# SCH_Calculator_YSWS_2026-07-11.net
KiCad netlist of a schematic drawn in EasyEDA
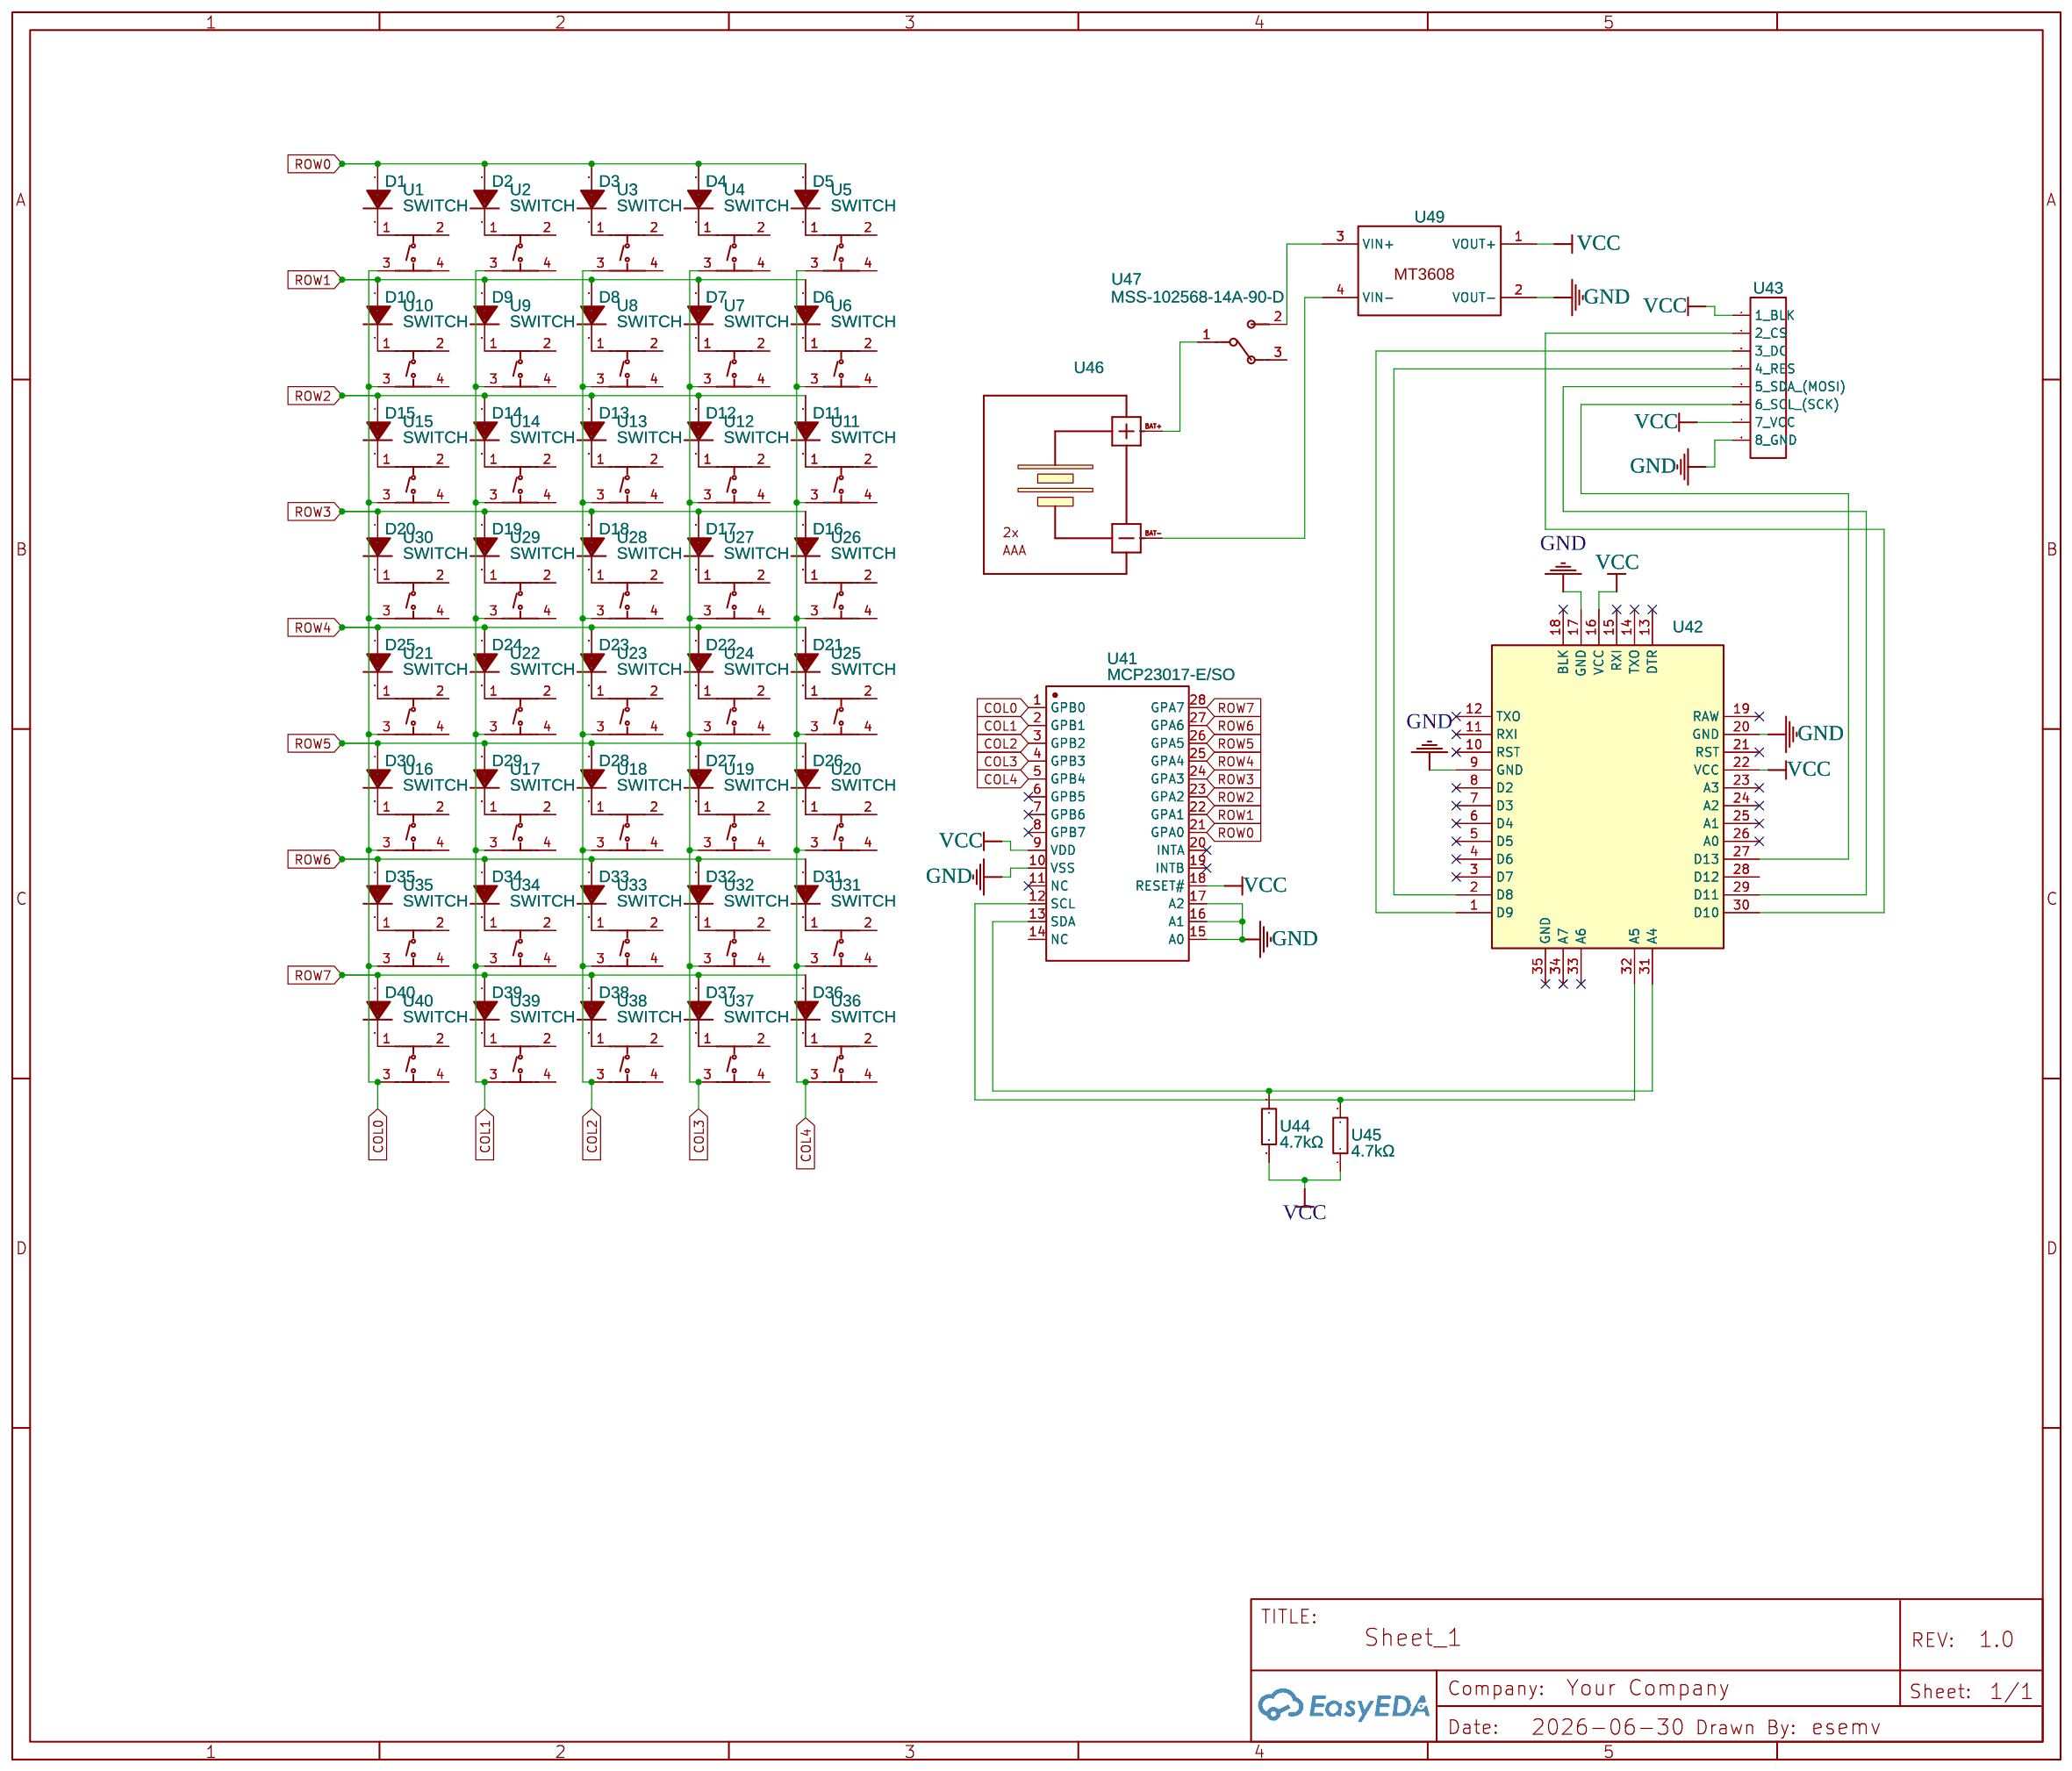
[diagram p0: schematic sheet]

(export (version "E")
  (design (tool "Eeschema 10.0.6"))
  (components
    (comp (ref "D1")
      (value "1N4148")
      (fields (field (name "Manufacturer") "ST(先科)"))
      (libsource (lib "") (part "1N4148"))
    )
    (comp (ref "D2")
      (value "1N4148")
      (fields (field (name "Manufacturer") "ST(先科)"))
      (libsource (lib "") (part "1N4148"))
    )
    (comp (ref "D3")
      (value "1N4148")
      (fields (field (name "Manufacturer") "ST(先科)"))
      (libsource (lib "") (part "1N4148"))
    )
    (comp (ref "D4")
      (value "1N4148")
      (fields (field (name "Manufacturer") "ST(先科)"))
      (libsource (lib "") (part "1N4148"))
    )
    (comp (ref "D5")
      (value "1N4148")
      (fields (field (name "Manufacturer") "ST(先科)"))
      (libsource (lib "") (part "1N4148"))
    )
    (comp (ref "D6")
      (value "1N4148")
      (fields (field (name "Manufacturer") "ST(先科)"))
      (libsource (lib "") (part "1N4148"))
    )
    (comp (ref "D7")
      (value "1N4148")
      (fields (field (name "Manufacturer") "ST(先科)"))
      (libsource (lib "") (part "1N4148"))
    )
    (comp (ref "D8")
      (value "1N4148")
      (fields (field (name "Manufacturer") "ST(先科)"))
      (libsource (lib "") (part "1N4148"))
    )
    (comp (ref "D9")
      (value "1N4148")
      (fields (field (name "Manufacturer") "ST(先科)"))
      (libsource (lib "") (part "1N4148"))
    )
    (comp (ref "D10")
      (value "1N4148")
      (fields (field (name "Manufacturer") "ST(先科)"))
      (libsource (lib "") (part "1N4148"))
    )
    (comp (ref "D11")
      (value "1N4148")
      (fields (field (name "Manufacturer") "ST(先科)"))
      (libsource (lib "") (part "1N4148"))
    )
    (comp (ref "D12")
      (value "1N4148")
      (fields (field (name "Manufacturer") "ST(先科)"))
      (libsource (lib "") (part "1N4148"))
    )
    (comp (ref "D13")
      (value "1N4148")
      (fields (field (name "Manufacturer") "ST(先科)"))
      (libsource (lib "") (part "1N4148"))
    )
    (comp (ref "D14")
      (value "1N4148")
      (fields (field (name "Manufacturer") "ST(先科)"))
      (libsource (lib "") (part "1N4148"))
    )
    (comp (ref "D15")
      (value "1N4148")
      (fields (field (name "Manufacturer") "ST(先科)"))
      (libsource (lib "") (part "1N4148"))
    )
    (comp (ref "D16")
      (value "1N4148")
      (fields (field (name "Manufacturer") "ST(先科)"))
      (libsource (lib "") (part "1N4148"))
    )
    (comp (ref "D17")
      (value "1N4148")
      (fields (field (name "Manufacturer") "ST(先科)"))
      (libsource (lib "") (part "1N4148"))
    )
    (comp (ref "D18")
      (value "1N4148")
      (fields (field (name "Manufacturer") "ST(先科)"))
      (libsource (lib "") (part "1N4148"))
    )
    (comp (ref "D19")
      (value "1N4148")
      (fields (field (name "Manufacturer") "ST(先科)"))
      (libsource (lib "") (part "1N4148"))
    )
    (comp (ref "D20")
      (value "1N4148")
      (fields (field (name "Manufacturer") "ST(先科)"))
      (libsource (lib "") (part "1N4148"))
    )
    (comp (ref "D21")
      (value "1N4148")
      (fields (field (name "Manufacturer") "ST(先科)"))
      (libsource (lib "") (part "1N4148"))
    )
    (comp (ref "D22")
      (value "1N4148")
      (fields (field (name "Manufacturer") "ST(先科)"))
      (libsource (lib "") (part "1N4148"))
    )
    (comp (ref "D23")
      (value "1N4148")
      (fields (field (name "Manufacturer") "ST(先科)"))
      (libsource (lib "") (part "1N4148"))
    )
    (comp (ref "D24")
      (value "1N4148")
      (fields (field (name "Manufacturer") "ST(先科)"))
      (libsource (lib "") (part "1N4148"))
    )
    (comp (ref "D25")
      (value "1N4148")
      (fields (field (name "Manufacturer") "ST(先科)"))
      (libsource (lib "") (part "1N4148"))
    )
    (comp (ref "D26")
      (value "1N4148")
      (fields (field (name "Manufacturer") "ST(先科)"))
      (libsource (lib "") (part "1N4148"))
    )
    (comp (ref "D27")
      (value "1N4148")
      (fields (field (name "Manufacturer") "ST(先科)"))
      (libsource (lib "") (part "1N4148"))
    )
    (comp (ref "D28")
      (value "1N4148")
      (fields (field (name "Manufacturer") "ST(先科)"))
      (libsource (lib "") (part "1N4148"))
    )
    (comp (ref "D29")
      (value "1N4148")
      (fields (field (name "Manufacturer") "ST(先科)"))
      (libsource (lib "") (part "1N4148"))
    )
    (comp (ref "D30")
      (value "1N4148")
      (fields (field (name "Manufacturer") "ST(先科)"))
      (libsource (lib "") (part "1N4148"))
    )
    (comp (ref "D31")
      (value "1N4148")
      (fields (field (name "Manufacturer") "ST(先科)"))
      (libsource (lib "") (part "1N4148"))
    )
    (comp (ref "D32")
      (value "1N4148")
      (fields (field (name "Manufacturer") "ST(先科)"))
      (libsource (lib "") (part "1N4148"))
    )
    (comp (ref "D33")
      (value "1N4148")
      (fields (field (name "Manufacturer") "ST(先科)"))
      (libsource (lib "") (part "1N4148"))
    )
    (comp (ref "D34")
      (value "1N4148")
      (fields (field (name "Manufacturer") "ST(先科)"))
      (libsource (lib "") (part "1N4148"))
    )
    (comp (ref "D35")
      (value "1N4148")
      (fields (field (name "Manufacturer") "ST(先科)"))
      (libsource (lib "") (part "1N4148"))
    )
    (comp (ref "D36")
      (value "1N4148")
      (fields (field (name "Manufacturer") "ST(先科)"))
      (libsource (lib "") (part "1N4148"))
    )
    (comp (ref "D37")
      (value "1N4148")
      (fields (field (name "Manufacturer") "ST(先科)"))
      (libsource (lib "") (part "1N4148"))
    )
    (comp (ref "D38")
      (value "1N4148")
      (fields (field (name "Manufacturer") "ST(先科)"))
      (libsource (lib "") (part "1N4148"))
    )
    (comp (ref "D39")
      (value "1N4148")
      (fields (field (name "Manufacturer") "ST(先科)"))
      (libsource (lib "") (part "1N4148"))
    )
    (comp (ref "D40")
      (value "1N4148")
      (fields (field (name "Manufacturer") "ST(先科)"))
      (libsource (lib "") (part "1N4148"))
    )
    (comp (ref "U1")
      (value "SWITCH")
      (fields
        (field (name "Manufacturer Part") "ZX-QC1212-7.0CJ")
        (field (name "Manufacturer") "Megastar(兆星)")
      )
      (libsource (lib "") (part "ZX-QC1212-7.0CJ"))
    )
    (comp (ref "U2")
      (value "SWITCH")
      (fields
        (field (name "Manufacturer Part") "ZX-QC1212-7.0CJ")
        (field (name "Manufacturer") "Megastar(兆星)")
      )
      (libsource (lib "") (part "ZX-QC1212-7.0CJ"))
    )
    (comp (ref "U3")
      (value "SWITCH")
      (fields
        (field (name "Manufacturer Part") "ZX-QC1212-7.0CJ")
        (field (name "Manufacturer") "Megastar(兆星)")
      )
      (libsource (lib "") (part "ZX-QC1212-7.0CJ"))
    )
    (comp (ref "U4")
      (value "SWITCH")
      (fields
        (field (name "Manufacturer Part") "ZX-QC1212-7.0CJ")
        (field (name "Manufacturer") "Megastar(兆星)")
      )
      (libsource (lib "") (part "ZX-QC1212-7.0CJ"))
    )
    (comp (ref "U5")
      (value "SWITCH")
      (fields
        (field (name "Manufacturer Part") "ZX-QC1212-7.0CJ")
        (field (name "Manufacturer") "Megastar(兆星)")
      )
      (libsource (lib "") (part "ZX-QC1212-7.0CJ"))
    )
    (comp (ref "U6")
      (value "SWITCH")
      (fields
        (field (name "Manufacturer Part") "ZX-QC1212-7.0CJ")
        (field (name "Manufacturer") "Megastar(兆星)")
      )
      (libsource (lib "") (part "ZX-QC1212-7.0CJ"))
    )
    (comp (ref "U7")
      (value "SWITCH")
      (fields
        (field (name "Manufacturer Part") "ZX-QC1212-7.0CJ")
        (field (name "Manufacturer") "Megastar(兆星)")
      )
      (libsource (lib "") (part "ZX-QC1212-7.0CJ"))
    )
    (comp (ref "U8")
      (value "SWITCH")
      (fields
        (field (name "Manufacturer Part") "ZX-QC1212-7.0CJ")
        (field (name "Manufacturer") "Megastar(兆星)")
      )
      (libsource (lib "") (part "ZX-QC1212-7.0CJ"))
    )
    (comp (ref "U9")
      (value "SWITCH")
      (fields
        (field (name "Manufacturer Part") "ZX-QC1212-7.0CJ")
        (field (name "Manufacturer") "Megastar(兆星)")
      )
      (libsource (lib "") (part "ZX-QC1212-7.0CJ"))
    )
    (comp (ref "U10")
      (value "SWITCH")
      (fields
        (field (name "Manufacturer Part") "ZX-QC1212-7.0CJ")
        (field (name "Manufacturer") "Megastar(兆星)")
      )
      (libsource (lib "") (part "ZX-QC1212-7.0CJ"))
    )
    (comp (ref "U11")
      (value "SWITCH")
      (fields
        (field (name "Manufacturer Part") "ZX-QC1212-7.0CJ")
        (field (name "Manufacturer") "Megastar(兆星)")
      )
      (libsource (lib "") (part "ZX-QC1212-7.0CJ"))
    )
    (comp (ref "U12")
      (value "SWITCH")
      (fields
        (field (name "Manufacturer Part") "ZX-QC1212-7.0CJ")
        (field (name "Manufacturer") "Megastar(兆星)")
      )
      (libsource (lib "") (part "ZX-QC1212-7.0CJ"))
    )
    (comp (ref "U13")
      (value "SWITCH")
      (fields
        (field (name "Manufacturer Part") "ZX-QC1212-7.0CJ")
        (field (name "Manufacturer") "Megastar(兆星)")
      )
      (libsource (lib "") (part "ZX-QC1212-7.0CJ"))
    )
    (comp (ref "U14")
      (value "SWITCH")
      (fields
        (field (name "Manufacturer Part") "ZX-QC1212-7.0CJ")
        (field (name "Manufacturer") "Megastar(兆星)")
      )
      (libsource (lib "") (part "ZX-QC1212-7.0CJ"))
    )
    (comp (ref "U15")
      (value "SWITCH")
      (fields
        (field (name "Manufacturer Part") "ZX-QC1212-7.0CJ")
        (field (name "Manufacturer") "Megastar(兆星)")
      )
      (libsource (lib "") (part "ZX-QC1212-7.0CJ"))
    )
    (comp (ref "U16")
      (value "SWITCH")
      (fields
        (field (name "Manufacturer Part") "ZX-QC1212-7.0CJ")
        (field (name "Manufacturer") "Megastar(兆星)")
      )
      (libsource (lib "") (part "ZX-QC1212-7.0CJ"))
    )
    (comp (ref "U17")
      (value "SWITCH")
      (fields
        (field (name "Manufacturer Part") "ZX-QC1212-7.0CJ")
        (field (name "Manufacturer") "Megastar(兆星)")
      )
      (libsource (lib "") (part "ZX-QC1212-7.0CJ"))
    )
    (comp (ref "U18")
      (value "SWITCH")
      (fields
        (field (name "Manufacturer Part") "ZX-QC1212-7.0CJ")
        (field (name "Manufacturer") "Megastar(兆星)")
      )
      (libsource (lib "") (part "ZX-QC1212-7.0CJ"))
    )
    (comp (ref "U19")
      (value "SWITCH")
      (fields
        (field (name "Manufacturer Part") "ZX-QC1212-7.0CJ")
        (field (name "Manufacturer") "Megastar(兆星)")
      )
      (libsource (lib "") (part "ZX-QC1212-7.0CJ"))
    )
    (comp (ref "U20")
      (value "SWITCH")
      (fields
        (field (name "Manufacturer Part") "ZX-QC1212-7.0CJ")
        (field (name "Manufacturer") "Megastar(兆星)")
      )
      (libsource (lib "") (part "ZX-QC1212-7.0CJ"))
    )
    (comp (ref "U21")
      (value "SWITCH")
      (fields
        (field (name "Manufacturer Part") "ZX-QC1212-7.0CJ")
        (field (name "Manufacturer") "Megastar(兆星)")
      )
      (libsource (lib "") (part "ZX-QC1212-7.0CJ"))
    )
    (comp (ref "U22")
      (value "SWITCH")
      (fields
        (field (name "Manufacturer Part") "ZX-QC1212-7.0CJ")
        (field (name "Manufacturer") "Megastar(兆星)")
      )
      (libsource (lib "") (part "ZX-QC1212-7.0CJ"))
    )
    (comp (ref "U23")
      (value "SWITCH")
      (fields
        (field (name "Manufacturer Part") "ZX-QC1212-7.0CJ")
        (field (name "Manufacturer") "Megastar(兆星)")
      )
      (libsource (lib "") (part "ZX-QC1212-7.0CJ"))
    )
    (comp (ref "U24")
      (value "SWITCH")
      (fields
        (field (name "Manufacturer Part") "ZX-QC1212-7.0CJ")
        (field (name "Manufacturer") "Megastar(兆星)")
      )
      (libsource (lib "") (part "ZX-QC1212-7.0CJ"))
    )
    (comp (ref "U25")
      (value "SWITCH")
      (fields
        (field (name "Manufacturer Part") "ZX-QC1212-7.0CJ")
        (field (name "Manufacturer") "Megastar(兆星)")
      )
      (libsource (lib "") (part "ZX-QC1212-7.0CJ"))
    )
    (comp (ref "U26")
      (value "SWITCH")
      (fields
        (field (name "Manufacturer Part") "ZX-QC1212-7.0CJ")
        (field (name "Manufacturer") "Megastar(兆星)")
      )
      (libsource (lib "") (part "ZX-QC1212-7.0CJ"))
    )
    (comp (ref "U27")
      (value "SWITCH")
      (fields
        (field (name "Manufacturer Part") "ZX-QC1212-7.0CJ")
        (field (name "Manufacturer") "Megastar(兆星)")
      )
      (libsource (lib "") (part "ZX-QC1212-7.0CJ"))
    )
    (comp (ref "U28")
      (value "SWITCH")
      (fields
        (field (name "Manufacturer Part") "ZX-QC1212-7.0CJ")
        (field (name "Manufacturer") "Megastar(兆星)")
      )
      (libsource (lib "") (part "ZX-QC1212-7.0CJ"))
    )
    (comp (ref "U29")
      (value "SWITCH")
      (fields
        (field (name "Manufacturer Part") "ZX-QC1212-7.0CJ")
        (field (name "Manufacturer") "Megastar(兆星)")
      )
      (libsource (lib "") (part "ZX-QC1212-7.0CJ"))
    )
    (comp (ref "U30")
      (value "SWITCH")
      (fields
        (field (name "Manufacturer Part") "ZX-QC1212-7.0CJ")
        (field (name "Manufacturer") "Megastar(兆星)")
      )
      (libsource (lib "") (part "ZX-QC1212-7.0CJ"))
    )
    (comp (ref "U31")
      (value "SWITCH")
      (fields
        (field (name "Manufacturer Part") "ZX-QC1212-7.0CJ")
        (field (name "Manufacturer") "Megastar(兆星)")
      )
      (libsource (lib "") (part "ZX-QC1212-7.0CJ"))
    )
    (comp (ref "U32")
      (value "SWITCH")
      (fields
        (field (name "Manufacturer Part") "ZX-QC1212-7.0CJ")
        (field (name "Manufacturer") "Megastar(兆星)")
      )
      (libsource (lib "") (part "ZX-QC1212-7.0CJ"))
    )
    (comp (ref "U33")
      (value "SWITCH")
      (fields
        (field (name "Manufacturer Part") "ZX-QC1212-7.0CJ")
        (field (name "Manufacturer") "Megastar(兆星)")
      )
      (libsource (lib "") (part "ZX-QC1212-7.0CJ"))
    )
    (comp (ref "U34")
      (value "SWITCH")
      (fields
        (field (name "Manufacturer Part") "ZX-QC1212-7.0CJ")
        (field (name "Manufacturer") "Megastar(兆星)")
      )
      (libsource (lib "") (part "ZX-QC1212-7.0CJ"))
    )
    (comp (ref "U35")
      (value "SWITCH")
      (fields
        (field (name "Manufacturer Part") "ZX-QC1212-7.0CJ")
        (field (name "Manufacturer") "Megastar(兆星)")
      )
      (libsource (lib "") (part "ZX-QC1212-7.0CJ"))
    )
    (comp (ref "U36")
      (value "SWITCH")
      (fields
        (field (name "Manufacturer Part") "ZX-QC1212-7.0CJ")
        (field (name "Manufacturer") "Megastar(兆星)")
      )
      (libsource (lib "") (part "ZX-QC1212-7.0CJ"))
    )
    (comp (ref "U37")
      (value "SWITCH")
      (fields
        (field (name "Manufacturer Part") "ZX-QC1212-7.0CJ")
        (field (name "Manufacturer") "Megastar(兆星)")
      )
      (libsource (lib "") (part "ZX-QC1212-7.0CJ"))
    )
    (comp (ref "U38")
      (value "SWITCH")
      (fields
        (field (name "Manufacturer Part") "ZX-QC1212-7.0CJ")
        (field (name "Manufacturer") "Megastar(兆星)")
      )
      (libsource (lib "") (part "ZX-QC1212-7.0CJ"))
    )
    (comp (ref "U39")
      (value "SWITCH")
      (fields
        (field (name "Manufacturer Part") "ZX-QC1212-7.0CJ")
        (field (name "Manufacturer") "Megastar(兆星)")
      )
      (libsource (lib "") (part "ZX-QC1212-7.0CJ"))
    )
    (comp (ref "U40")
      (value "SWITCH")
      (fields
        (field (name "Manufacturer Part") "ZX-QC1212-7.0CJ")
        (field (name "Manufacturer") "Megastar(兆星)")
      )
      (libsource (lib "") (part "ZX-QC1212-7.0CJ"))
    )
    (comp (ref "U41")
      (value "MCP23017-E/SO")
      (fields (field (name "Manufacturer") "MICROCHIP(美国微芯)"))
      (libsource (lib "") (part "MCP23017-E/SO"))
    )
    (comp (ref "U42") (value "NO") (libsource (lib "") (part "ARDUINO PRO MINI - 3.3V")))
    (comp (ref "U43") (value "NO") (libsource (lib "") (part "HDR-M-2.54_1x8")))
    (comp (ref "U44")
      (value "4.7kΩ")
      (fields (field (name "Manufacturer Part") "CR1/4W-4K7±5%-OT26") (field (name "Manufacturer") "VO(翔胜)"))
      (libsource (lib "") (part "CR1/4W-4K7±5%-OT26"))
    )
    (comp (ref "U45")
      (value "4.7kΩ")
      (fields (field (name "Manufacturer Part") "CR1/4W-4K7±5%-OT26") (field (name "Manufacturer") "VO(翔胜)"))
      (libsource (lib "") (part "CR1/4W-4K7±5%-OT26"))
    )
    (comp (ref "U46") (value "NO") (libsource (lib "") (part "BATTERY-HOLDER-2AAA")))
    (comp (ref "U47")
      (value "MSS-102568-14A-90-D")
      (fields (field (name "Manufacturer") "CUI"))
      (libsource (lib "") (part "MSS-102568-14A-90-D"))
    )
    (comp (ref "U49") (value "NO") (libsource (lib "") (part "MT3608 module")))
  )
  (nets
    (net (code "1") (name "COL0") (class "Default")
      (node (ref "U1") (pin "3") (pinfunction "3_3") (pintype "unspecified"))
      (node (ref "U10") (pin "3") (pinfunction "3_3") (pintype "unspecified"))
      (node (ref "U15") (pin "3") (pinfunction "3_3") (pintype "unspecified"))
      (node (ref "U16") (pin "3") (pinfunction "3_3") (pintype "unspecified"))
      (node (ref "U21") (pin "3") (pinfunction "3_3") (pintype "unspecified"))
      (node (ref "U30") (pin "3") (pinfunction "3_3") (pintype "unspecified"))
      (node (ref "U35") (pin "3") (pinfunction "3_3") (pintype "unspecified"))
      (node (ref "U40") (pin "3") (pinfunction "3_3") (pintype "unspecified"))
      (node (ref "U41") (pin "1") (pinfunction "GPB0_1") (pintype "unspecified"))
    )
    (net (code "2") (name "COL1") (class "Default")
      (node (ref "U14") (pin "3") (pinfunction "3_3") (pintype "unspecified"))
      (node (ref "U17") (pin "3") (pinfunction "3_3") (pintype "unspecified"))
      (node (ref "U2") (pin "3") (pinfunction "3_3") (pintype "unspecified"))
      (node (ref "U22") (pin "3") (pinfunction "3_3") (pintype "unspecified"))
      (node (ref "U29") (pin "3") (pinfunction "3_3") (pintype "unspecified"))
      (node (ref "U34") (pin "3") (pinfunction "3_3") (pintype "unspecified"))
      (node (ref "U39") (pin "3") (pinfunction "3_3") (pintype "unspecified"))
      (node (ref "U41") (pin "2") (pinfunction "GPB1_2") (pintype "unspecified"))
      (node (ref "U9") (pin "3") (pinfunction "3_3") (pintype "unspecified"))
    )
    (net (code "3") (name "COL2") (class "Default")
      (node (ref "U13") (pin "3") (pinfunction "3_3") (pintype "unspecified"))
      (node (ref "U18") (pin "3") (pinfunction "3_3") (pintype "unspecified"))
      (node (ref "U23") (pin "3") (pinfunction "3_3") (pintype "unspecified"))
      (node (ref "U28") (pin "3") (pinfunction "3_3") (pintype "unspecified"))
      (node (ref "U3") (pin "3") (pinfunction "3_3") (pintype "unspecified"))
      (node (ref "U33") (pin "3") (pinfunction "3_3") (pintype "unspecified"))
      (node (ref "U38") (pin "3") (pinfunction "3_3") (pintype "unspecified"))
      (node (ref "U41") (pin "3") (pinfunction "GPB2_3") (pintype "unspecified"))
      (node (ref "U8") (pin "3") (pinfunction "3_3") (pintype "unspecified"))
    )
    (net (code "4") (name "COL3") (class "Default")
      (node (ref "U12") (pin "3") (pinfunction "3_3") (pintype "unspecified"))
      (node (ref "U19") (pin "3") (pinfunction "3_3") (pintype "unspecified"))
      (node (ref "U24") (pin "3") (pinfunction "3_3") (pintype "unspecified"))
      (node (ref "U27") (pin "3") (pinfunction "3_3") (pintype "unspecified"))
      (node (ref "U32") (pin "3") (pinfunction "3_3") (pintype "unspecified"))
      (node (ref "U37") (pin "3") (pinfunction "3_3") (pintype "unspecified"))
      (node (ref "U4") (pin "3") (pinfunction "3_3") (pintype "unspecified"))
      (node (ref "U41") (pin "4") (pinfunction "GPB3_4") (pintype "unspecified"))
      (node (ref "U7") (pin "3") (pinfunction "3_3") (pintype "unspecified"))
    )
    (net (code "5") (name "COL4") (class "Default")
      (node (ref "U11") (pin "3") (pinfunction "3_3") (pintype "unspecified"))
      (node (ref "U20") (pin "3") (pinfunction "3_3") (pintype "unspecified"))
      (node (ref "U25") (pin "3") (pinfunction "3_3") (pintype "unspecified"))
      (node (ref "U26") (pin "3") (pinfunction "3_3") (pintype "unspecified"))
      (node (ref "U31") (pin "3") (pinfunction "3_3") (pintype "unspecified"))
      (node (ref "U36") (pin "3") (pinfunction "3_3") (pintype "unspecified"))
      (node (ref "U41") (pin "5") (pinfunction "GPB4_5") (pintype "unspecified"))
      (node (ref "U5") (pin "3") (pinfunction "3_3") (pintype "unspecified"))
      (node (ref "U6") (pin "3") (pinfunction "3_3") (pintype "unspecified"))
    )
    (net (code "6") (name "GND") (class "Default")
      (node (ref "U41") (pin "10") (pinfunction "VSS_10") (pintype "unspecified"))
      (node (ref "U41") (pin "15") (pinfunction "A0_15") (pintype "unspecified"))
      (node (ref "U41") (pin "16") (pinfunction "A1_16") (pintype "unspecified"))
      (node (ref "U41") (pin "17") (pinfunction "A2_17") (pintype "unspecified"))
      (node (ref "U42") (pin "17") (pinfunction "GND_17") (pintype "unspecified"))
      (node (ref "U42") (pin "20") (pinfunction "GND_20") (pintype "unspecified"))
      (node (ref "U42") (pin "9") (pinfunction "GND_9") (pintype "unspecified"))
      (node (ref "U43") (pin "8") (pinfunction "8_GND_8") (pintype "unspecified"))
      (node (ref "U49") (pin "2") (pinfunction "VOUT-_2") (pintype "unspecified"))
    )
    (net (code "7") (name "Net-(D1-C)") (class "Default")
      (node (ref "D1") (pin "2") (pinfunction "C_2") (pintype "unspecified"))
      (node (ref "U1") (pin "1") (pinfunction "1_1") (pintype "unspecified"))
    )
    (net (code "8") (name "Net-(D2-C)") (class "Default")
      (node (ref "D2") (pin "2") (pinfunction "C_2") (pintype "unspecified"))
      (node (ref "U2") (pin "1") (pinfunction "1_1") (pintype "unspecified"))
    )
    (net (code "9") (name "Net-(D3-C)") (class "Default")
      (node (ref "D3") (pin "2") (pinfunction "C_2") (pintype "unspecified"))
      (node (ref "U3") (pin "1") (pinfunction "1_1") (pintype "unspecified"))
    )
    (net (code "10") (name "Net-(D4-C)") (class "Default")
      (node (ref "D4") (pin "2") (pinfunction "C_2") (pintype "unspecified"))
      (node (ref "U4") (pin "1") (pinfunction "1_1") (pintype "unspecified"))
    )
    (net (code "11") (name "Net-(D5-C)") (class "Default")
      (node (ref "D5") (pin "2") (pinfunction "C_2") (pintype "unspecified"))
      (node (ref "U5") (pin "1") (pinfunction "1_1") (pintype "unspecified"))
    )
    (net (code "12") (name "Net-(D6-C)") (class "Default")
      (node (ref "D6") (pin "2") (pinfunction "C_2") (pintype "unspecified"))
      (node (ref "U6") (pin "1") (pinfunction "1_1") (pintype "unspecified"))
    )
    (net (code "13") (name "Net-(D7-C)") (class "Default")
      (node (ref "D7") (pin "2") (pinfunction "C_2") (pintype "unspecified"))
      (node (ref "U7") (pin "1") (pinfunction "1_1") (pintype "unspecified"))
    )
    (net (code "14") (name "Net-(D8-C)") (class "Default")
      (node (ref "D8") (pin "2") (pinfunction "C_2") (pintype "unspecified"))
      (node (ref "U8") (pin "1") (pinfunction "1_1") (pintype "unspecified"))
    )
    (net (code "15") (name "Net-(D9-C)") (class "Default")
      (node (ref "D9") (pin "2") (pinfunction "C_2") (pintype "unspecified"))
      (node (ref "U9") (pin "1") (pinfunction "1_1") (pintype "unspecified"))
    )
    (net (code "16") (name "Net-(D10-C)") (class "Default")
      (node (ref "D10") (pin "2") (pinfunction "C_2") (pintype "unspecified"))
      (node (ref "U10") (pin "1") (pinfunction "1_1") (pintype "unspecified"))
    )
    (net (code "17") (name "Net-(D11-C)") (class "Default")
      (node (ref "D11") (pin "2") (pinfunction "C_2") (pintype "unspecified"))
      (node (ref "U11") (pin "1") (pinfunction "1_1") (pintype "unspecified"))
    )
    (net (code "18") (name "Net-(D12-C)") (class "Default")
      (node (ref "D12") (pin "2") (pinfunction "C_2") (pintype "unspecified"))
      (node (ref "U12") (pin "1") (pinfunction "1_1") (pintype "unspecified"))
    )
    (net (code "19") (name "Net-(D13-C)") (class "Default")
      (node (ref "D13") (pin "2") (pinfunction "C_2") (pintype "unspecified"))
      (node (ref "U13") (pin "1") (pinfunction "1_1") (pintype "unspecified"))
    )
    (net (code "20") (name "Net-(D14-C)") (class "Default")
      (node (ref "D14") (pin "2") (pinfunction "C_2") (pintype "unspecified"))
      (node (ref "U14") (pin "1") (pinfunction "1_1") (pintype "unspecified"))
    )
    (net (code "21") (name "Net-(D15-C)") (class "Default")
      (node (ref "D15") (pin "2") (pinfunction "C_2") (pintype "unspecified"))
      (node (ref "U15") (pin "1") (pinfunction "1_1") (pintype "unspecified"))
    )
    (net (code "22") (name "Net-(D16-C)") (class "Default")
      (node (ref "D16") (pin "2") (pinfunction "C_2") (pintype "unspecified"))
      (node (ref "U26") (pin "1") (pinfunction "1_1") (pintype "unspecified"))
    )
    (net (code "23") (name "Net-(D17-C)") (class "Default")
      (node (ref "D17") (pin "2") (pinfunction "C_2") (pintype "unspecified"))
      (node (ref "U27") (pin "1") (pinfunction "1_1") (pintype "unspecified"))
    )
    (net (code "24") (name "Net-(D18-C)") (class "Default")
      (node (ref "D18") (pin "2") (pinfunction "C_2") (pintype "unspecified"))
      (node (ref "U28") (pin "1") (pinfunction "1_1") (pintype "unspecified"))
    )
    (net (code "25") (name "Net-(D19-C)") (class "Default")
      (node (ref "D19") (pin "2") (pinfunction "C_2") (pintype "unspecified"))
      (node (ref "U29") (pin "1") (pinfunction "1_1") (pintype "unspecified"))
    )
    (net (code "26") (name "Net-(D20-C)") (class "Default")
      (node (ref "D20") (pin "2") (pinfunction "C_2") (pintype "unspecified"))
      (node (ref "U30") (pin "1") (pinfunction "1_1") (pintype "unspecified"))
    )
    (net (code "27") (name "Net-(D21-C)") (class "Default")
      (node (ref "D21") (pin "2") (pinfunction "C_2") (pintype "unspecified"))
      (node (ref "U25") (pin "1") (pinfunction "1_1") (pintype "unspecified"))
    )
    (net (code "28") (name "Net-(D22-C)") (class "Default")
      (node (ref "D22") (pin "2") (pinfunction "C_2") (pintype "unspecified"))
      (node (ref "U24") (pin "1") (pinfunction "1_1") (pintype "unspecified"))
    )
    (net (code "29") (name "Net-(D23-C)") (class "Default")
      (node (ref "D23") (pin "2") (pinfunction "C_2") (pintype "unspecified"))
      (node (ref "U23") (pin "1") (pinfunction "1_1") (pintype "unspecified"))
    )
    (net (code "30") (name "Net-(D24-C)") (class "Default")
      (node (ref "D24") (pin "2") (pinfunction "C_2") (pintype "unspecified"))
      (node (ref "U22") (pin "1") (pinfunction "1_1") (pintype "unspecified"))
    )
    (net (code "31") (name "Net-(D25-C)") (class "Default")
      (node (ref "D25") (pin "2") (pinfunction "C_2") (pintype "unspecified"))
      (node (ref "U21") (pin "1") (pinfunction "1_1") (pintype "unspecified"))
    )
    (net (code "32") (name "Net-(D26-C)") (class "Default")
      (node (ref "D26") (pin "2") (pinfunction "C_2") (pintype "unspecified"))
      (node (ref "U20") (pin "1") (pinfunction "1_1") (pintype "unspecified"))
    )
    (net (code "33") (name "Net-(D27-C)") (class "Default")
      (node (ref "D27") (pin "2") (pinfunction "C_2") (pintype "unspecified"))
      (node (ref "U19") (pin "1") (pinfunction "1_1") (pintype "unspecified"))
    )
    (net (code "34") (name "Net-(D28-C)") (class "Default")
      (node (ref "D28") (pin "2") (pinfunction "C_2") (pintype "unspecified"))
      (node (ref "U18") (pin "1") (pinfunction "1_1") (pintype "unspecified"))
    )
    (net (code "35") (name "Net-(D29-C)") (class "Default")
      (node (ref "D29") (pin "2") (pinfunction "C_2") (pintype "unspecified"))
      (node (ref "U17") (pin "1") (pinfunction "1_1") (pintype "unspecified"))
    )
    (net (code "36") (name "Net-(D30-C)") (class "Default")
      (node (ref "D30") (pin "2") (pinfunction "C_2") (pintype "unspecified"))
      (node (ref "U16") (pin "1") (pinfunction "1_1") (pintype "unspecified"))
    )
    (net (code "37") (name "Net-(D31-C)") (class "Default")
      (node (ref "D31") (pin "2") (pinfunction "C_2") (pintype "unspecified"))
      (node (ref "U31") (pin "1") (pinfunction "1_1") (pintype "unspecified"))
    )
    (net (code "38") (name "Net-(D32-C)") (class "Default")
      (node (ref "D32") (pin "2") (pinfunction "C_2") (pintype "unspecified"))
      (node (ref "U32") (pin "1") (pinfunction "1_1") (pintype "unspecified"))
    )
    (net (code "39") (name "Net-(D33-C)") (class "Default")
      (node (ref "D33") (pin "2") (pinfunction "C_2") (pintype "unspecified"))
      (node (ref "U33") (pin "1") (pinfunction "1_1") (pintype "unspecified"))
    )
    (net (code "40") (name "Net-(D34-C)") (class "Default")
      (node (ref "D34") (pin "2") (pinfunction "C_2") (pintype "unspecified"))
      (node (ref "U34") (pin "1") (pinfunction "1_1") (pintype "unspecified"))
    )
    (net (code "41") (name "Net-(D35-C)") (class "Default")
      (node (ref "D35") (pin "2") (pinfunction "C_2") (pintype "unspecified"))
      (node (ref "U35") (pin "1") (pinfunction "1_1") (pintype "unspecified"))
    )
    (net (code "42") (name "Net-(D36-C)") (class "Default")
      (node (ref "D36") (pin "2") (pinfunction "C_2") (pintype "unspecified"))
      (node (ref "U36") (pin "1") (pinfunction "1_1") (pintype "unspecified"))
    )
    (net (code "43") (name "Net-(D37-C)") (class "Default")
      (node (ref "D37") (pin "2") (pinfunction "C_2") (pintype "unspecified"))
      (node (ref "U37") (pin "1") (pinfunction "1_1") (pintype "unspecified"))
    )
    (net (code "44") (name "Net-(D38-C)") (class "Default")
      (node (ref "D38") (pin "2") (pinfunction "C_2") (pintype "unspecified"))
      (node (ref "U38") (pin "1") (pinfunction "1_1") (pintype "unspecified"))
    )
    (net (code "45") (name "Net-(D39-C)") (class "Default")
      (node (ref "D39") (pin "2") (pinfunction "C_2") (pintype "unspecified"))
      (node (ref "U39") (pin "1") (pinfunction "1_1") (pintype "unspecified"))
    )
    (net (code "46") (name "Net-(D40-C)") (class "Default")
      (node (ref "D40") (pin "2") (pinfunction "C_2") (pintype "unspecified"))
      (node (ref "U40") (pin "1") (pinfunction "1_1") (pintype "unspecified"))
    )
    (net (code "47") (name "Net-(U41-SCL)") (class "Default")
      (node (ref "U41") (pin "12") (pinfunction "SCL_12") (pintype "unspecified"))
      (node (ref "U42") (pin "32") (pinfunction "A5_32") (pintype "unspecified"))
      (node (ref "U45") (pin "2") (pinfunction "2_2") (pintype "unspecified"))
    )
    (net (code "48") (name "Net-(U41-SDA)") (class "Default")
      (node (ref "U41") (pin "13") (pinfunction "SDA_13") (pintype "unspecified"))
      (node (ref "U42") (pin "31") (pinfunction "A4_31") (pintype "unspecified"))
      (node (ref "U44") (pin "2") (pinfunction "2_2") (pintype "unspecified"))
    )
    (net (code "49") (name "Net-(U42-D8)") (class "Default")
      (node (ref "U42") (pin "2") (pinfunction "D8_2") (pintype "unspecified"))
      (node (ref "U43") (pin "4") (pinfunction "4_RES_4") (pintype "unspecified"))
    )
    (net (code "50") (name "Net-(U42-D9)") (class "Default")
      (node (ref "U42") (pin "1") (pinfunction "D9_1") (pintype "unspecified"))
      (node (ref "U43") (pin "3") (pinfunction "3_DC_3") (pintype "unspecified"))
    )
    (net (code "51") (name "Net-(U42-D10)") (class "Default")
      (node (ref "U42") (pin "30") (pinfunction "D10_30") (pintype "unspecified"))
      (node (ref "U43") (pin "2") (pinfunction "2_CS_2") (pintype "unspecified"))
    )
    (net (code "52") (name "Net-(U42-D11)") (class "Default")
      (node (ref "U42") (pin "29") (pinfunction "D11_29") (pintype "unspecified"))
      (node (ref "U43") (pin "5") (pinfunction "5_SDA_(MOSI)_5") (pintype "unspecified"))
    )
    (net (code "53") (name "Net-(U42-D13)") (class "Default")
      (node (ref "U42") (pin "27") (pinfunction "D13_27") (pintype "unspecified"))
      (node (ref "U43") (pin "6") (pinfunction "6_SCL_(SCK)_6") (pintype "unspecified"))
    )
    (net (code "54") (name "Net-(U46-PadBAT+)") (class "Default")
      (node (ref "U46") (pin "BAT+") (pinfunction "BAT+_BAT+") (pintype "bidirectional"))
      (node (ref "U47") (pin "1") (pinfunction "1_1") (pintype "unspecified"))
    )
    (net (code "55") (name "Net-(U49-VIN+)") (class "Default")
      (node (ref "U47") (pin "2") (pinfunction "2_2") (pintype "unspecified"))
      (node (ref "U49") (pin "3") (pinfunction "VIN+_3") (pintype "unspecified"))
    )
    (net (code "56") (name "Net-(U49-VIN-)") (class "Default")
      (node (ref "U46") (pin "BAT-") (pinfunction "BAT-_BAT-") (pintype "bidirectional"))
      (node (ref "U49") (pin "4") (pinfunction "VIN-_4") (pintype "unspecified"))
    )
    (net (code "57") (name "ROW0") (class "Default")
      (node (ref "D1") (pin "1") (pinfunction "A_1") (pintype "unspecified"))
      (node (ref "D2") (pin "1") (pinfunction "A_1") (pintype "unspecified"))
      (node (ref "D3") (pin "1") (pinfunction "A_1") (pintype "unspecified"))
      (node (ref "D4") (pin "1") (pinfunction "A_1") (pintype "unspecified"))
      (node (ref "D5") (pin "1") (pinfunction "A_1") (pintype "unspecified"))
      (node (ref "U41") (pin "21") (pinfunction "GPA0_21") (pintype "unspecified"))
    )
    (net (code "58") (name "ROW1") (class "Default")
      (node (ref "D10") (pin "1") (pinfunction "A_1") (pintype "unspecified"))
      (node (ref "D6") (pin "1") (pinfunction "A_1") (pintype "unspecified"))
      (node (ref "D7") (pin "1") (pinfunction "A_1") (pintype "unspecified"))
      (node (ref "D8") (pin "1") (pinfunction "A_1") (pintype "unspecified"))
      (node (ref "D9") (pin "1") (pinfunction "A_1") (pintype "unspecified"))
      (node (ref "U41") (pin "22") (pinfunction "GPA1_22") (pintype "unspecified"))
    )
    (net (code "59") (name "ROW2") (class "Default")
      (node (ref "D11") (pin "1") (pinfunction "A_1") (pintype "unspecified"))
      (node (ref "D12") (pin "1") (pinfunction "A_1") (pintype "unspecified"))
      (node (ref "D13") (pin "1") (pinfunction "A_1") (pintype "unspecified"))
      (node (ref "D14") (pin "1") (pinfunction "A_1") (pintype "unspecified"))
      (node (ref "D15") (pin "1") (pinfunction "A_1") (pintype "unspecified"))
      (node (ref "U41") (pin "23") (pinfunction "GPA2_23") (pintype "unspecified"))
    )
    (net (code "60") (name "ROW3") (class "Default")
      (node (ref "D16") (pin "1") (pinfunction "A_1") (pintype "unspecified"))
      (node (ref "D17") (pin "1") (pinfunction "A_1") (pintype "unspecified"))
      (node (ref "D18") (pin "1") (pinfunction "A_1") (pintype "unspecified"))
      (node (ref "D19") (pin "1") (pinfunction "A_1") (pintype "unspecified"))
      (node (ref "D20") (pin "1") (pinfunction "A_1") (pintype "unspecified"))
      (node (ref "U41") (pin "24") (pinfunction "GPA3_24") (pintype "unspecified"))
    )
    (net (code "61") (name "ROW4") (class "Default")
      (node (ref "D21") (pin "1") (pinfunction "A_1") (pintype "unspecified"))
      (node (ref "D22") (pin "1") (pinfunction "A_1") (pintype "unspecified"))
      (node (ref "D23") (pin "1") (pinfunction "A_1") (pintype "unspecified"))
      (node (ref "D24") (pin "1") (pinfunction "A_1") (pintype "unspecified"))
      (node (ref "D25") (pin "1") (pinfunction "A_1") (pintype "unspecified"))
      (node (ref "U41") (pin "25") (pinfunction "GPA4_25") (pintype "unspecified"))
    )
    (net (code "62") (name "ROW5") (class "Default")
      (node (ref "D26") (pin "1") (pinfunction "A_1") (pintype "unspecified"))
      (node (ref "D27") (pin "1") (pinfunction "A_1") (pintype "unspecified"))
      (node (ref "D28") (pin "1") (pinfunction "A_1") (pintype "unspecified"))
      (node (ref "D29") (pin "1") (pinfunction "A_1") (pintype "unspecified"))
      (node (ref "D30") (pin "1") (pinfunction "A_1") (pintype "unspecified"))
      (node (ref "U41") (pin "26") (pinfunction "GPA5_26") (pintype "unspecified"))
    )
    (net (code "63") (name "ROW6") (class "Default")
      (node (ref "D31") (pin "1") (pinfunction "A_1") (pintype "unspecified"))
      (node (ref "D32") (pin "1") (pinfunction "A_1") (pintype "unspecified"))
      (node (ref "D33") (pin "1") (pinfunction "A_1") (pintype "unspecified"))
      (node (ref "D34") (pin "1") (pinfunction "A_1") (pintype "unspecified"))
      (node (ref "D35") (pin "1") (pinfunction "A_1") (pintype "unspecified"))
      (node (ref "U41") (pin "27") (pinfunction "GPA6_27") (pintype "unspecified"))
    )
    (net (code "64") (name "ROW7") (class "Default")
      (node (ref "D36") (pin "1") (pinfunction "A_1") (pintype "unspecified"))
      (node (ref "D37") (pin "1") (pinfunction "A_1") (pintype "unspecified"))
      (node (ref "D38") (pin "1") (pinfunction "A_1") (pintype "unspecified"))
      (node (ref "D39") (pin "1") (pinfunction "A_1") (pintype "unspecified"))
      (node (ref "D40") (pin "1") (pinfunction "A_1") (pintype "unspecified"))
      (node (ref "U41") (pin "28") (pinfunction "GPA7_28") (pintype "unspecified"))
    )
    (net (code "65") (name "VCC") (class "Default")
      (node (ref "U41") (pin "18") (pinfunction "RESET#_18") (pintype "unspecified"))
      (node (ref "U41") (pin "9") (pinfunction "VDD_9") (pintype "unspecified"))
      (node (ref "U42") (pin "16") (pinfunction "VCC_16") (pintype "unspecified"))
      (node (ref "U42") (pin "22") (pinfunction "VCC_22") (pintype "unspecified"))
      (node (ref "U43") (pin "1") (pinfunction "1_BLK_1") (pintype "unspecified"))
      (node (ref "U43") (pin "7") (pinfunction "7_VCC_7") (pintype "unspecified"))
      (node (ref "U44") (pin "1") (pinfunction "1_1") (pintype "unspecified"))
      (node (ref "U45") (pin "1") (pinfunction "1_1") (pintype "unspecified"))
      (node (ref "U49") (pin "1") (pinfunction "VOUT+_1") (pintype "unspecified"))
    )
    (net (code "66") (name "unconnected-(U1-Pad2)") (class "Default")
      (node (ref "U1") (pin "2") (pinfunction "2_2") (pintype "unspecified"))
    )
    (net (code "67") (name "unconnected-(U1-Pad4)") (class "Default")
      (node (ref "U1") (pin "4") (pinfunction "4_4") (pintype "unspecified"))
    )
    (net (code "68") (name "unconnected-(U2-Pad2)") (class "Default")
      (node (ref "U2") (pin "2") (pinfunction "2_2") (pintype "unspecified"))
    )
    (net (code "69") (name "unconnected-(U2-Pad4)") (class "Default")
      (node (ref "U2") (pin "4") (pinfunction "4_4") (pintype "unspecified"))
    )
    (net (code "70") (name "unconnected-(U3-Pad2)") (class "Default")
      (node (ref "U3") (pin "2") (pinfunction "2_2") (pintype "unspecified"))
    )
    (net (code "71") (name "unconnected-(U3-Pad4)") (class "Default")
      (node (ref "U3") (pin "4") (pinfunction "4_4") (pintype "unspecified"))
    )
    (net (code "72") (name "unconnected-(U4-Pad2)") (class "Default")
      (node (ref "U4") (pin "2") (pinfunction "2_2") (pintype "unspecified"))
    )
    (net (code "73") (name "unconnected-(U4-Pad4)") (class "Default")
      (node (ref "U4") (pin "4") (pinfunction "4_4") (pintype "unspecified"))
    )
    (net (code "74") (name "unconnected-(U5-Pad2)") (class "Default")
      (node (ref "U5") (pin "2") (pinfunction "2_2") (pintype "unspecified"))
    )
    (net (code "75") (name "unconnected-(U5-Pad4)") (class "Default")
      (node (ref "U5") (pin "4") (pinfunction "4_4") (pintype "unspecified"))
    )
    (net (code "76") (name "unconnected-(U6-Pad2)") (class "Default")
      (node (ref "U6") (pin "2") (pinfunction "2_2") (pintype "unspecified"))
    )
    (net (code "77") (name "unconnected-(U6-Pad4)") (class "Default")
      (node (ref "U6") (pin "4") (pinfunction "4_4") (pintype "unspecified"))
    )
    (net (code "78") (name "unconnected-(U7-Pad2)") (class "Default")
      (node (ref "U7") (pin "2") (pinfunction "2_2") (pintype "unspecified"))
    )
    (net (code "79") (name "unconnected-(U7-Pad4)") (class "Default")
      (node (ref "U7") (pin "4") (pinfunction "4_4") (pintype "unspecified"))
    )
    (net (code "80") (name "unconnected-(U8-Pad2)") (class "Default")
      (node (ref "U8") (pin "2") (pinfunction "2_2") (pintype "unspecified"))
    )
    (net (code "81") (name "unconnected-(U8-Pad4)") (class "Default")
      (node (ref "U8") (pin "4") (pinfunction "4_4") (pintype "unspecified"))
    )
    (net (code "82") (name "unconnected-(U9-Pad2)") (class "Default")
      (node (ref "U9") (pin "2") (pinfunction "2_2") (pintype "unspecified"))
    )
    (net (code "83") (name "unconnected-(U9-Pad4)") (class "Default")
      (node (ref "U9") (pin "4") (pinfunction "4_4") (pintype "unspecified"))
    )
    (net (code "84") (name "unconnected-(U10-Pad2)") (class "Default")
      (node (ref "U10") (pin "2") (pinfunction "2_2") (pintype "unspecified"))
    )
    (net (code "85") (name "unconnected-(U10-Pad4)") (class "Default")
      (node (ref "U10") (pin "4") (pinfunction "4_4") (pintype "unspecified"))
    )
    (net (code "86") (name "unconnected-(U11-Pad2)") (class "Default")
      (node (ref "U11") (pin "2") (pinfunction "2_2") (pintype "unspecified"))
    )
    (net (code "87") (name "unconnected-(U11-Pad4)") (class "Default")
      (node (ref "U11") (pin "4") (pinfunction "4_4") (pintype "unspecified"))
    )
    (net (code "88") (name "unconnected-(U12-Pad2)") (class "Default")
      (node (ref "U12") (pin "2") (pinfunction "2_2") (pintype "unspecified"))
    )
    (net (code "89") (name "unconnected-(U12-Pad4)") (class "Default")
      (node (ref "U12") (pin "4") (pinfunction "4_4") (pintype "unspecified"))
    )
    (net (code "90") (name "unconnected-(U13-Pad2)") (class "Default")
      (node (ref "U13") (pin "2") (pinfunction "2_2") (pintype "unspecified"))
    )
    (net (code "91") (name "unconnected-(U13-Pad4)") (class "Default")
      (node (ref "U13") (pin "4") (pinfunction "4_4") (pintype "unspecified"))
    )
    (net (code "92") (name "unconnected-(U14-Pad2)") (class "Default")
      (node (ref "U14") (pin "2") (pinfunction "2_2") (pintype "unspecified"))
    )
    (net (code "93") (name "unconnected-(U14-Pad4)") (class "Default")
      (node (ref "U14") (pin "4") (pinfunction "4_4") (pintype "unspecified"))
    )
    (net (code "94") (name "unconnected-(U15-Pad2)") (class "Default")
      (node (ref "U15") (pin "2") (pinfunction "2_2") (pintype "unspecified"))
    )
    (net (code "95") (name "unconnected-(U15-Pad4)") (class "Default")
      (node (ref "U15") (pin "4") (pinfunction "4_4") (pintype "unspecified"))
    )
    (net (code "96") (name "unconnected-(U16-Pad2)") (class "Default")
      (node (ref "U16") (pin "2") (pinfunction "2_2") (pintype "unspecified"))
    )
    (net (code "97") (name "unconnected-(U16-Pad4)") (class "Default")
      (node (ref "U16") (pin "4") (pinfunction "4_4") (pintype "unspecified"))
    )
    (net (code "98") (name "unconnected-(U17-Pad2)") (class "Default")
      (node (ref "U17") (pin "2") (pinfunction "2_2") (pintype "unspecified"))
    )
    (net (code "99") (name "unconnected-(U17-Pad4)") (class "Default")
      (node (ref "U17") (pin "4") (pinfunction "4_4") (pintype "unspecified"))
    )
    (net (code "100") (name "unconnected-(U18-Pad2)") (class "Default")
      (node (ref "U18") (pin "2") (pinfunction "2_2") (pintype "unspecified"))
    )
    (net (code "101") (name "unconnected-(U18-Pad4)") (class "Default")
      (node (ref "U18") (pin "4") (pinfunction "4_4") (pintype "unspecified"))
    )
    (net (code "102") (name "unconnected-(U19-Pad2)") (class "Default")
      (node (ref "U19") (pin "2") (pinfunction "2_2") (pintype "unspecified"))
    )
    (net (code "103") (name "unconnected-(U19-Pad4)") (class "Default")
      (node (ref "U19") (pin "4") (pinfunction "4_4") (pintype "unspecified"))
    )
    (net (code "104") (name "unconnected-(U20-Pad2)") (class "Default")
      (node (ref "U20") (pin "2") (pinfunction "2_2") (pintype "unspecified"))
    )
    (net (code "105") (name "unconnected-(U20-Pad4)") (class "Default")
      (node (ref "U20") (pin "4") (pinfunction "4_4") (pintype "unspecified"))
    )
    (net (code "106") (name "unconnected-(U21-Pad2)") (class "Default")
      (node (ref "U21") (pin "2") (pinfunction "2_2") (pintype "unspecified"))
    )
    (net (code "107") (name "unconnected-(U21-Pad4)") (class "Default")
      (node (ref "U21") (pin "4") (pinfunction "4_4") (pintype "unspecified"))
    )
    (net (code "108") (name "unconnected-(U22-Pad2)") (class "Default")
      (node (ref "U22") (pin "2") (pinfunction "2_2") (pintype "unspecified"))
    )
    (net (code "109") (name "unconnected-(U22-Pad4)") (class "Default")
      (node (ref "U22") (pin "4") (pinfunction "4_4") (pintype "unspecified"))
    )
    (net (code "110") (name "unconnected-(U23-Pad2)") (class "Default")
      (node (ref "U23") (pin "2") (pinfunction "2_2") (pintype "unspecified"))
    )
    (net (code "111") (name "unconnected-(U23-Pad4)") (class "Default")
      (node (ref "U23") (pin "4") (pinfunction "4_4") (pintype "unspecified"))
    )
    (net (code "112") (name "unconnected-(U24-Pad2)") (class "Default")
      (node (ref "U24") (pin "2") (pinfunction "2_2") (pintype "unspecified"))
    )
    (net (code "113") (name "unconnected-(U24-Pad4)") (class "Default")
      (node (ref "U24") (pin "4") (pinfunction "4_4") (pintype "unspecified"))
    )
    (net (code "114") (name "unconnected-(U25-Pad2)") (class "Default")
      (node (ref "U25") (pin "2") (pinfunction "2_2") (pintype "unspecified"))
    )
    (net (code "115") (name "unconnected-(U25-Pad4)") (class "Default")
      (node (ref "U25") (pin "4") (pinfunction "4_4") (pintype "unspecified"))
    )
    (net (code "116") (name "unconnected-(U26-Pad2)") (class "Default")
      (node (ref "U26") (pin "2") (pinfunction "2_2") (pintype "unspecified"))
    )
    (net (code "117") (name "unconnected-(U26-Pad4)") (class "Default")
      (node (ref "U26") (pin "4") (pinfunction "4_4") (pintype "unspecified"))
    )
    (net (code "118") (name "unconnected-(U27-Pad2)") (class "Default")
      (node (ref "U27") (pin "2") (pinfunction "2_2") (pintype "unspecified"))
    )
    (net (code "119") (name "unconnected-(U27-Pad4)") (class "Default")
      (node (ref "U27") (pin "4") (pinfunction "4_4") (pintype "unspecified"))
    )
    (net (code "120") (name "unconnected-(U28-Pad2)") (class "Default")
      (node (ref "U28") (pin "2") (pinfunction "2_2") (pintype "unspecified"))
    )
    (net (code "121") (name "unconnected-(U28-Pad4)") (class "Default")
      (node (ref "U28") (pin "4") (pinfunction "4_4") (pintype "unspecified"))
    )
    (net (code "122") (name "unconnected-(U29-Pad2)") (class "Default")
      (node (ref "U29") (pin "2") (pinfunction "2_2") (pintype "unspecified"))
    )
    (net (code "123") (name "unconnected-(U29-Pad4)") (class "Default")
      (node (ref "U29") (pin "4") (pinfunction "4_4") (pintype "unspecified"))
    )
    (net (code "124") (name "unconnected-(U30-Pad2)") (class "Default")
      (node (ref "U30") (pin "2") (pinfunction "2_2") (pintype "unspecified"))
    )
    (net (code "125") (name "unconnected-(U30-Pad4)") (class "Default")
      (node (ref "U30") (pin "4") (pinfunction "4_4") (pintype "unspecified"))
    )
    (net (code "126") (name "unconnected-(U31-Pad2)") (class "Default")
      (node (ref "U31") (pin "2") (pinfunction "2_2") (pintype "unspecified"))
    )
    (net (code "127") (name "unconnected-(U31-Pad4)") (class "Default")
      (node (ref "U31") (pin "4") (pinfunction "4_4") (pintype "unspecified"))
    )
    (net (code "128") (name "unconnected-(U32-Pad2)") (class "Default")
      (node (ref "U32") (pin "2") (pinfunction "2_2") (pintype "unspecified"))
    )
    (net (code "129") (name "unconnected-(U32-Pad4)") (class "Default")
      (node (ref "U32") (pin "4") (pinfunction "4_4") (pintype "unspecified"))
    )
    (net (code "130") (name "unconnected-(U33-Pad2)") (class "Default")
      (node (ref "U33") (pin "2") (pinfunction "2_2") (pintype "unspecified"))
    )
    (net (code "131") (name "unconnected-(U33-Pad4)") (class "Default")
      (node (ref "U33") (pin "4") (pinfunction "4_4") (pintype "unspecified"))
    )
    (net (code "132") (name "unconnected-(U34-Pad2)") (class "Default")
      (node (ref "U34") (pin "2") (pinfunction "2_2") (pintype "unspecified"))
    )
    (net (code "133") (name "unconnected-(U34-Pad4)") (class "Default")
      (node (ref "U34") (pin "4") (pinfunction "4_4") (pintype "unspecified"))
    )
    (net (code "134") (name "unconnected-(U35-Pad2)") (class "Default")
      (node (ref "U35") (pin "2") (pinfunction "2_2") (pintype "unspecified"))
    )
    (net (code "135") (name "unconnected-(U35-Pad4)") (class "Default")
      (node (ref "U35") (pin "4") (pinfunction "4_4") (pintype "unspecified"))
    )
    (net (code "136") (name "unconnected-(U36-Pad2)") (class "Default")
      (node (ref "U36") (pin "2") (pinfunction "2_2") (pintype "unspecified"))
    )
    (net (code "137") (name "unconnected-(U36-Pad4)") (class "Default")
      (node (ref "U36") (pin "4") (pinfunction "4_4") (pintype "unspecified"))
    )
    (net (code "138") (name "unconnected-(U37-Pad2)") (class "Default")
      (node (ref "U37") (pin "2") (pinfunction "2_2") (pintype "unspecified"))
    )
    (net (code "139") (name "unconnected-(U37-Pad4)") (class "Default")
      (node (ref "U37") (pin "4") (pinfunction "4_4") (pintype "unspecified"))
    )
    (net (code "140") (name "unconnected-(U38-Pad2)") (class "Default")
      (node (ref "U38") (pin "2") (pinfunction "2_2") (pintype "unspecified"))
    )
    (net (code "141") (name "unconnected-(U38-Pad4)") (class "Default")
      (node (ref "U38") (pin "4") (pinfunction "4_4") (pintype "unspecified"))
    )
    (net (code "142") (name "unconnected-(U39-Pad2)") (class "Default")
      (node (ref "U39") (pin "2") (pinfunction "2_2") (pintype "unspecified"))
    )
    (net (code "143") (name "unconnected-(U39-Pad4)") (class "Default")
      (node (ref "U39") (pin "4") (pinfunction "4_4") (pintype "unspecified"))
    )
    (net (code "144") (name "unconnected-(U40-Pad2)") (class "Default")
      (node (ref "U40") (pin "2") (pinfunction "2_2") (pintype "unspecified"))
    )
    (net (code "145") (name "unconnected-(U40-Pad4)") (class "Default")
      (node (ref "U40") (pin "4") (pinfunction "4_4") (pintype "unspecified"))
    )
    (net (code "146") (name "unconnected-(U41-GPB5-Pad6)") (class "Default")
      (node (ref "U41") (pin "6") (pinfunction "GPB5_6") (pintype "unspecified+no_connect"))
    )
    (net (code "147") (name "unconnected-(U41-GPB6-Pad7)") (class "Default")
      (node (ref "U41") (pin "7") (pinfunction "GPB6_7") (pintype "unspecified+no_connect"))
    )
    (net (code "148") (name "unconnected-(U41-GPB7-Pad8)") (class "Default")
      (node (ref "U41") (pin "8") (pinfunction "GPB7_8") (pintype "unspecified+no_connect"))
    )
    (net (code "149") (name "unconnected-(U41-INTA-Pad20)") (class "Default")
      (node (ref "U41") (pin "20") (pinfunction "INTA_20") (pintype "unspecified+no_connect"))
    )
    (net (code "150") (name "unconnected-(U41-INTB-Pad19)") (class "Default")
      (node (ref "U41") (pin "19") (pinfunction "INTB_19") (pintype "unspecified+no_connect"))
    )
    (net (code "151") (name "unconnected-(U41-NC-Pad11)") (class "Default")
      (node (ref "U41") (pin "11") (pinfunction "NC_11") (pintype "unspecified+no_connect"))
    )
    (net (code "152") (name "unconnected-(U41-NC-Pad14)") (class "Default")
      (node (ref "U41") (pin "14") (pinfunction "NC_14") (pintype "unspecified"))
    )
    (net (code "153") (name "unconnected-(U42-A0-Pad26)") (class "Default")
      (node (ref "U42") (pin "26") (pinfunction "A0_26") (pintype "unspecified+no_connect"))
    )
    (net (code "154") (name "unconnected-(U42-A1-Pad25)") (class "Default")
      (node (ref "U42") (pin "25") (pinfunction "A1_25") (pintype "unspecified+no_connect"))
    )
    (net (code "155") (name "unconnected-(U42-A2-Pad24)") (class "Default")
      (node (ref "U42") (pin "24") (pinfunction "A2_24") (pintype "unspecified+no_connect"))
    )
    (net (code "156") (name "unconnected-(U42-A3-Pad23)") (class "Default")
      (node (ref "U42") (pin "23") (pinfunction "A3_23") (pintype "unspecified+no_connect"))
    )
    (net (code "157") (name "unconnected-(U42-A6-Pad33)") (class "Default")
      (node (ref "U42") (pin "33") (pinfunction "A6_33") (pintype "unspecified+no_connect"))
    )
    (net (code "158") (name "unconnected-(U42-A7-Pad34)") (class "Default")
      (node (ref "U42") (pin "34") (pinfunction "A7_34") (pintype "unspecified+no_connect"))
    )
    (net (code "159") (name "unconnected-(U42-BLK-Pad18)") (class "Default")
      (node (ref "U42") (pin "18") (pinfunction "BLK_18") (pintype "unspecified+no_connect"))
    )
    (net (code "160") (name "unconnected-(U42-D2-Pad8)") (class "Default")
      (node (ref "U42") (pin "8") (pinfunction "D2_8") (pintype "unspecified+no_connect"))
    )
    (net (code "161") (name "unconnected-(U42-D3-Pad7)") (class "Default")
      (node (ref "U42") (pin "7") (pinfunction "D3_7") (pintype "unspecified+no_connect"))
    )
    (net (code "162") (name "unconnected-(U42-D4-Pad6)") (class "Default")
      (node (ref "U42") (pin "6") (pinfunction "D4_6") (pintype "unspecified+no_connect"))
    )
    (net (code "163") (name "unconnected-(U42-D5-Pad5)") (class "Default")
      (node (ref "U42") (pin "5") (pinfunction "D5_5") (pintype "unspecified+no_connect"))
    )
    (net (code "164") (name "unconnected-(U42-D6-Pad4)") (class "Default")
      (node (ref "U42") (pin "4") (pinfunction "D6_4") (pintype "unspecified+no_connect"))
    )
    (net (code "165") (name "unconnected-(U42-D7-Pad3)") (class "Default")
      (node (ref "U42") (pin "3") (pinfunction "D7_3") (pintype "unspecified+no_connect"))
    )
    (net (code "166") (name "unconnected-(U42-D12-Pad28)") (class "Default")
      (node (ref "U42") (pin "28") (pinfunction "D12_28") (pintype "unspecified"))
    )
    (net (code "167") (name "unconnected-(U42-DTR-Pad13)") (class "Default")
      (node (ref "U42") (pin "13") (pinfunction "DTR_13") (pintype "unspecified+no_connect"))
    )
    (net (code "168") (name "unconnected-(U42-GND-Pad35)") (class "Default")
      (node (ref "U42") (pin "35") (pinfunction "GND_35") (pintype "unspecified+no_connect"))
    )
    (net (code "169") (name "unconnected-(U42-RAW-Pad19)") (class "Default")
      (node (ref "U42") (pin "19") (pinfunction "RAW_19") (pintype "unspecified+no_connect"))
    )
    (net (code "170") (name "unconnected-(U42-RST-Pad10)") (class "Default")
      (node (ref "U42") (pin "10") (pinfunction "RST_10") (pintype "unspecified+no_connect"))
    )
    (net (code "171") (name "unconnected-(U42-RST-Pad21)") (class "Default")
      (node (ref "U42") (pin "21") (pinfunction "RST_21") (pintype "unspecified+no_connect"))
    )
    (net (code "172") (name "unconnected-(U42-RXI-Pad11)") (class "Default")
      (node (ref "U42") (pin "11") (pinfunction "RXI_11") (pintype "unspecified+no_connect"))
    )
    (net (code "173") (name "unconnected-(U42-RXI-Pad15)") (class "Default")
      (node (ref "U42") (pin "15") (pinfunction "RXI_15") (pintype "unspecified+no_connect"))
    )
    (net (code "174") (name "unconnected-(U42-TXO-Pad12)") (class "Default")
      (node (ref "U42") (pin "12") (pinfunction "TXO_12") (pintype "unspecified+no_connect"))
    )
    (net (code "175") (name "unconnected-(U42-TXO-Pad14)") (class "Default")
      (node (ref "U42") (pin "14") (pinfunction "TXO_14") (pintype "unspecified+no_connect"))
    )
    (net (code "176") (name "unconnected-(U47-Pad3)") (class "Default")
      (node (ref "U47") (pin "3") (pinfunction "3_3") (pintype "unspecified"))
    )
  )
)
